# Connector_Sheet.net
KiCad netlist of a schematic drawn in Altium Designer
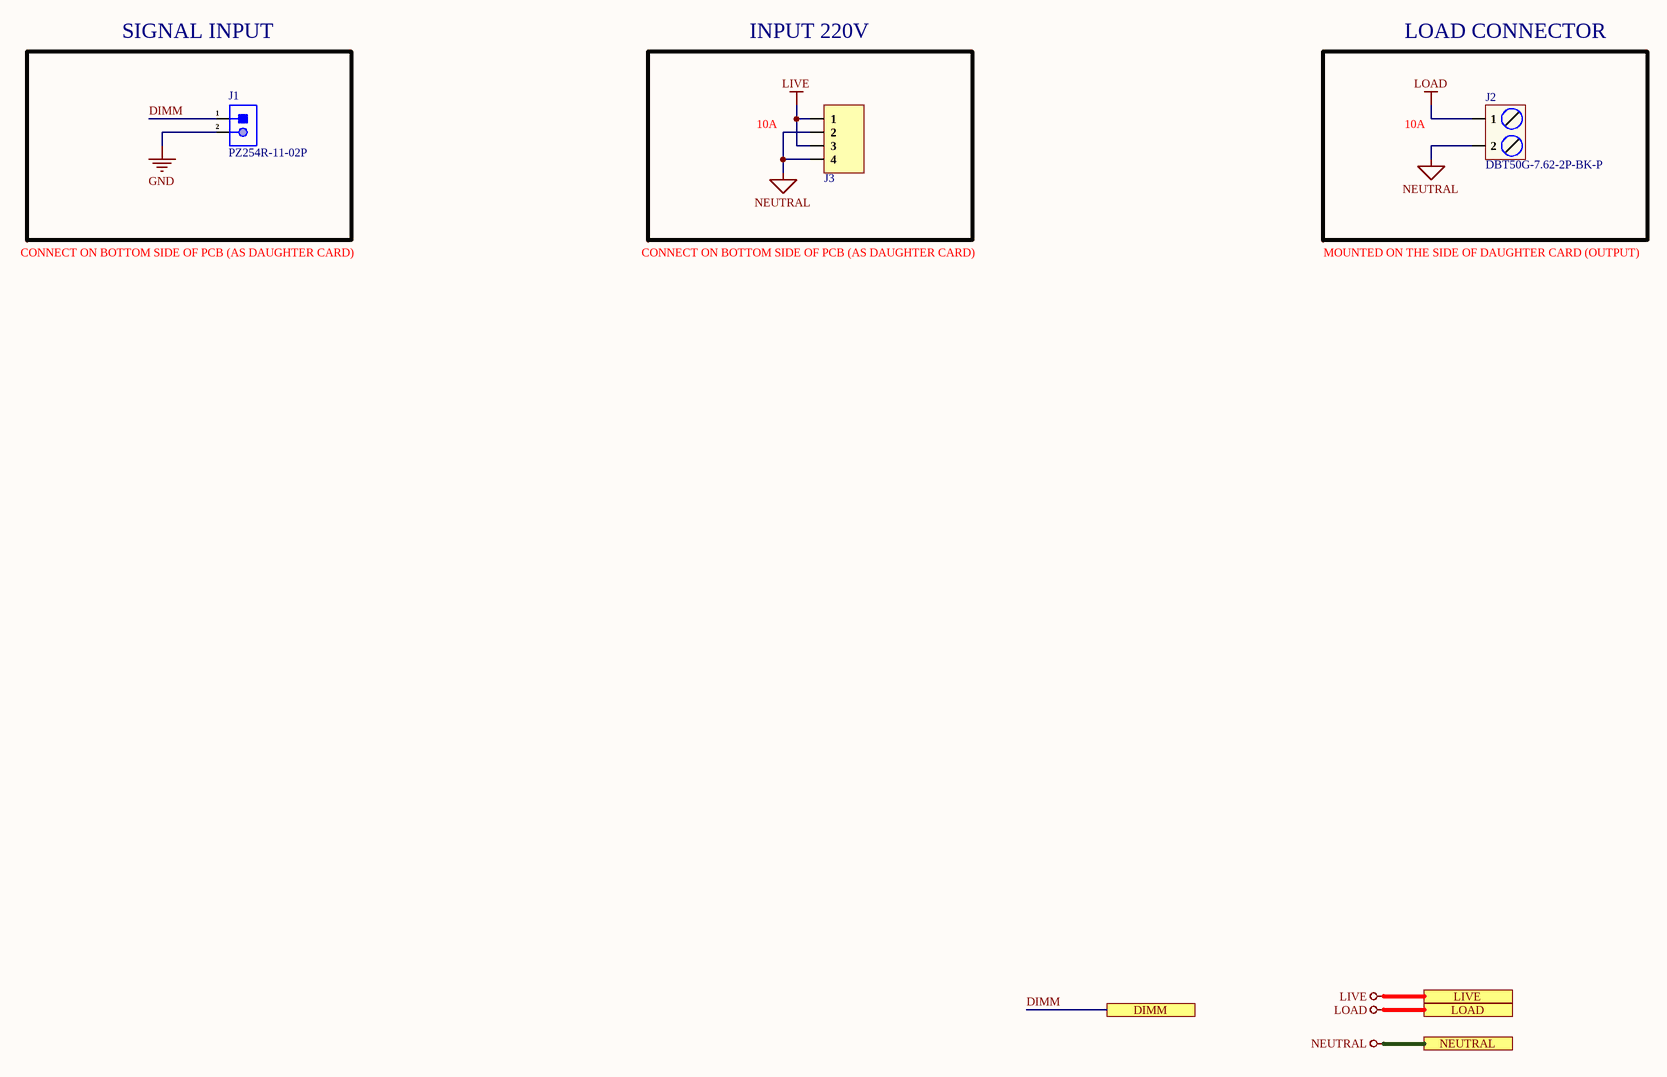
[diagram p0: Connector_Sheet.SchDoc]

(export (version "E")
  (design (tool "Eeschema 10.0.6"))
  (components
    (comp (ref "J1")
      (value "PZ254R-11-02P")
      (footprint "HDR1X2 (R/A Male)")
      (fields (field (name "MANUFACTURER") "XFCN") (field (name "LCSC PART NUMBER") "C492410"))
      (libsource (lib "eSpark Libraries") (part "PZ254R-11-02P"))
    )
    (comp (ref "J2")
      (value "DBT50G-7.62-2P-BK-P")
      (footprint "DBT50G-7.62-2P-BK-P")
      (fields (field (name "MANUFACTURER") "DORABO") (field (name "LCSC PART NUMBER") "C496127"))
      (libsource (lib "eSpark Libraries") (part "DBT50G-7.62-2P-BK-P"))
    )
    (comp (ref "J3")
      (value "0444280401")
      (description "Connector Header Through Hole, Right Angle 4 position 0.118\" (3.00mm)")
      (fields (field (name "MANUFACTURER") "Molex") (field (name "DIGIKEY PART NUMBER") "23-0444280401-ND"))
      (libsource (lib "SchLib") (part "0444280401"))
    )
  )
  (nets
    (net (code "1") (name "/DIMM") (class "Default")
      (node (ref "J1") (pin "1") (pinfunction "1_1") (pintype "passive"))
    )
    (net (code "2") (name "GND") (class "Default")
      (node (ref "J1") (pin "2") (pinfunction "2_2") (pintype "passive"))
    )
    (net (code "3") (name "LIVE") (class "Default")
      (node (ref "J3") (pin "1") (pinfunction "1_1") (pintype "passive"))
      (node (ref "J3") (pin "3") (pinfunction "3_3") (pintype "passive"))
    )
    (net (code "4") (name "LOAD") (class "Default")
      (node (ref "J2") (pin "1") (pinfunction "1_1") (pintype "passive"))
    )
    (net (code "5") (name "NEUTRAL") (class "Default")
      (node (ref "J2") (pin "2") (pinfunction "2_2") (pintype "passive"))
      (node (ref "J3") (pin "2") (pinfunction "2_2") (pintype "passive"))
      (node (ref "J3") (pin "4") (pinfunction "4_4") (pintype "passive"))
    )
  )
)
